# Undervoltage_Protection.net
KiCad netlist of a schematic drawn in Altium Designer
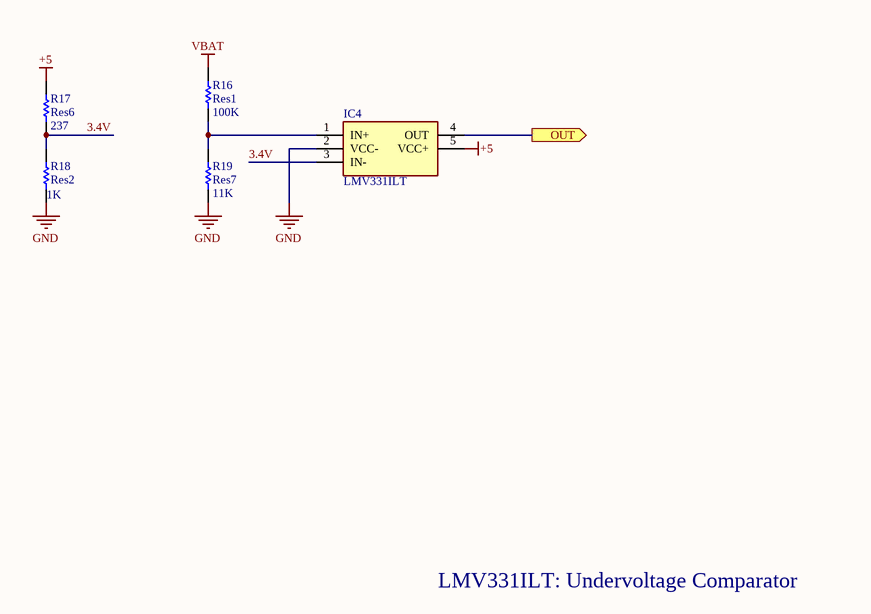
[diagram p0: Undervoltage Protection.SchDoc]

(export (version "E")
  (design (tool "Eeschema 10.0.6"))
  (components
    (comp (ref "IC4")
      (value "LMV331ILT")
      (footprint "SOT95P280X145-5N")
      (description "Integrated Circuit")
      (fields (field (name "MOUSER PART NUMBER") "511-LMV331ILT"))
      (libsource (lib "*") (part "LMV331ILT"))
    )
    (comp (ref "R16")
      (value "Res1")
      (footprint "0402")
      (description "Resistor")
      (fields (field (name "ALTIUM_VALUE") "100K") (field (name "PUBLISHER") "Altium Limited"))
      (libsource (lib "Miscellaneous Devices") (part "Res1"))
    )
    (comp (ref "R17")
      (value "Res6")
      (footprint "0402")
      (description "Resistor")
      (fields (field (name "ALTIUM_VALUE") "237") (field (name "PUBLISHER") "Altium Limited"))
      (libsource (lib "Miscellaneous Devices") (part "Res1"))
    )
    (comp (ref "R18")
      (value "Res2")
      (footprint "0402")
      (description "Resistor")
      (fields (field (name "ALTIUM_VALUE") "1K") (field (name "PUBLISHER") "Altium Limited"))
      (libsource (lib "Miscellaneous Devices") (part "Res1"))
    )
    (comp (ref "R19")
      (value "Res7")
      (footprint "0402")
      (description "Resistor")
      (fields (field (name "ALTIUM_VALUE") "11K") (field (name "PUBLISHER") "Altium Limited"))
      (libsource (lib "Miscellaneous Devices") (part "Res1"))
    )
  )
  (nets
    (net (code "1") (name "+5") (class "Default")
      (node (ref "IC4") (pin "5") (pinfunction "VCC+_5") (pintype "passive"))
      (node (ref "R17") (pin "1") (pinfunction "1_1") (pintype "passive"))
    )
    (net (code "2") (name "/3.4V") (class "Default")
      (node (ref "IC4") (pin "3") (pinfunction "IN-_3") (pintype "passive"))
      (node (ref "R17") (pin "2") (pinfunction "2_2") (pintype "passive"))
      (node (ref "R18") (pin "2") (pinfunction "2_2") (pintype "passive"))
    )
    (net (code "3") (name "/OUT") (class "Default")
      (node (ref "IC4") (pin "4") (pinfunction "OUT_4") (pintype "passive"))
    )
    (net (code "4") (name "GND") (class "Default")
      (node (ref "IC4") (pin "2") (pinfunction "VCC-_2") (pintype "passive"))
      (node (ref "R18") (pin "1") (pinfunction "1_1") (pintype "passive"))
      (node (ref "R19") (pin "1") (pinfunction "1_1") (pintype "passive"))
    )
    (net (code "5") (name "Net-(IC4-IN+)") (class "Default")
      (node (ref "IC4") (pin "1") (pinfunction "IN+_1") (pintype "passive"))
      (node (ref "R16") (pin "1") (pinfunction "1_1") (pintype "passive"))
      (node (ref "R19") (pin "2") (pinfunction "2_2") (pintype "passive"))
    )
    (net (code "6") (name "VBAT") (class "Default")
      (node (ref "R16") (pin "2") (pinfunction "2_2") (pintype "passive"))
    )
  )
)
